# TurboSpin.net
KiCad netlist of a schematic drawn in Altium Designer
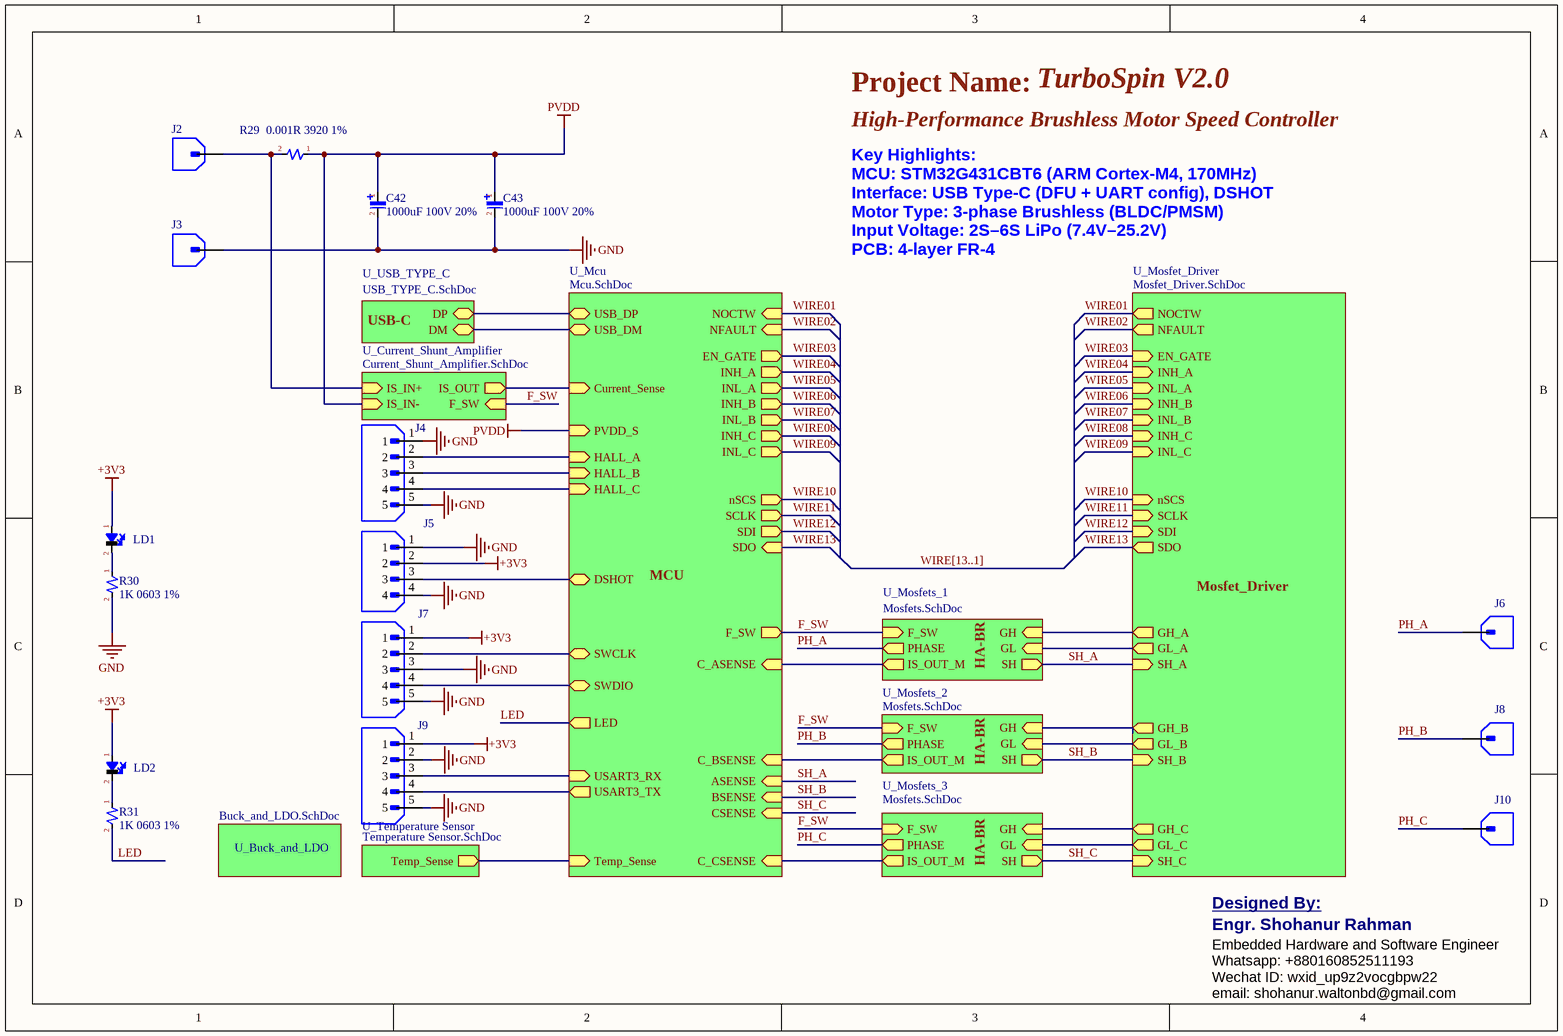
[diagram p0: TurboSpin.SchDoc]

(export (version "E")
  (design (tool "Eeschema 10.0.6"))
  (components
    (comp (ref "C42")
      (value "1000uF 100V 20%")
      (footprint "C_RADIAL")
      (libsource (lib "Walton_EED_13_05_2024") (part "Capacitor{gt}{gt} Polar"))
    )
    (comp (ref "C43")
      (value "1000uF 100V 20%")
      (footprint "C_RADIAL")
      (libsource (lib "Walton_EED_13_05_2024") (part "Capacitor{gt}{gt} Polar"))
    )
    (comp (ref "J2")
      (value "Connector>>B1B")
      (footprint "CN_1P_PAD")
      (description "Connector Header Through Hole 5 position 0.098 (2.50mm)")
      (fields (field (name "MF") "JST Sales") (field (name "MP") "B5B-XH-A"))
      (libsource (lib "Walton_EED_13_05_2024") (part "Connector{gt}{gt}B1B"))
    )
    (comp (ref "J3")
      (value "Connector>>B1B")
      (footprint "CN_1P_PAD")
      (description "Connector Header Through Hole 5 position 0.098 (2.50mm)")
      (fields (field (name "MF") "JST Sales") (field (name "MP") "B5B-XH-A"))
      (libsource (lib "Walton_EED_13_05_2024") (part "Connector{gt}{gt}B1B"))
    )
    (comp (ref "J4")
      (value "Connector>>B5B-XH-A")
      (footprint "CN_HDGC2001WV-S-4")
      (description "Connector Header Through Hole 5 position 0.098 (2.50mm)")
      (fields (field (name "MF") "JST Sales") (field (name "MP") "B5B-XH-A"))
      (libsource (lib "Walton_EED_13_05_2024") (part "Connector{gt}{gt}B5B-XH-A"))
    )
    (comp (ref "J5")
      (value "Connector>>B4B-XH-A")
      (footprint "CN_HDGC2001WV-S-3")
      (description "Connector Header Through Hole 5 position 0.098 (2.50mm)")
      (fields (field (name "MF") "JST Sales") (field (name "MP") "B5B-XH-A"))
      (libsource (lib "Walton_EED_13_05_2024") (part "Connector{gt}{gt}B4B-XH-A"))
    )
    (comp (ref "J6")
      (value "Connector>>B1B")
      (footprint "CN_1P_PAD")
      (description "Connector Header Through Hole 5 position 0.098 (2.50mm)")
      (fields (field (name "MF") "JST Sales") (field (name "MP") "B5B-XH-A"))
      (libsource (lib "") (part "Connector{gt}{gt}B1B_1"))
    )
    (comp (ref "J7")
      (value "Connector>>B5B-XH-A")
      (footprint "CN_HDGC2001WV-S-4")
      (description "Connector Header Through Hole 5 position 0.098 (2.50mm)")
      (fields (field (name "MF") "JST Sales") (field (name "MP") "B5B-XH-A"))
      (libsource (lib "Walton_EED_13_05_2024") (part "Connector{gt}{gt}B5B-XH-A"))
    )
    (comp (ref "J8")
      (value "Connector>>B1B")
      (footprint "CN_1P_PAD")
      (description "Connector Header Through Hole 5 position 0.098 (2.50mm)")
      (fields (field (name "MF") "JST Sales") (field (name "MP") "B5B-XH-A"))
      (libsource (lib "") (part "Connector{gt}{gt}B1B_1"))
    )
    (comp (ref "J9")
      (value "Connector>>B5B-XH-A")
      (footprint "CN_HDGC2001WV-S-4")
      (description "Connector Header Through Hole 5 position 0.098 (2.50mm)")
      (fields (field (name "MF") "JST Sales") (field (name "MP") "B5B-XH-A"))
      (libsource (lib "Walton_EED_13_05_2024") (part "Connector{gt}{gt}B5B-XH-A"))
    )
    (comp (ref "J10")
      (value "Connector>>B1B")
      (footprint "CN_1P_PAD")
      (description "Connector Header Through Hole 5 position 0.098 (2.50mm)")
      (fields (field (name "MF") "JST Sales") (field (name "MP") "B5B-XH-A"))
      (libsource (lib "") (part "Connector{gt}{gt}B1B_1"))
    )
    (comp (ref "LD1")
      (value "1.8Vf  25mA  5mW")
      (footprint "LED_0603_red")
      (libsource (lib "Walton_EED_13_05_2024") (part "LED{gt}{gt} General Purpose"))
    )
    (comp (ref "LD2")
      (value "1.8Vf  25mA  5mW")
      (footprint "LED_0603_red")
      (libsource (lib "Walton_EED_13_05_2024") (part "LED{gt}{gt} General Purpose"))
    )
    (comp (ref "R29")
      (value "0.001R 3920 1%")
      (footprint "R_3920")
      (description "RES 0603 20%")
      (libsource (lib "Walton_EED") (part "Resistor{gt}{gt} General Purpose"))
    )
    (comp (ref "R30")
      (value "1K 0603 1%")
      (footprint "R_0603")
      (description "RES 0603 20%")
      (libsource (lib "Walton_EED") (part "Resistor{gt}{gt} General Purpose"))
    )
    (comp (ref "R31")
      (value "1K 0603 1%")
      (footprint "R_0603")
      (description "RES 0603 20%")
      (libsource (lib "Walton_EED") (part "Resistor{gt}{gt} General Purpose"))
    )
  )
  (nets
    (net (code "10") (name "+3V3") (class "Default")
      (node (ref "J5") (pin "2") (pinfunction "2_2") (pintype "passive"))
      (node (ref "J7") (pin "1") (pinfunction "1_1") (pintype "passive"))
      (node (ref "J9") (pin "1") (pinfunction "1_1") (pintype "passive"))
      (node (ref "LD1") (pin "1") (pinfunction "vdd_1") (pintype "passive"))
      (node (ref "LD2") (pin "1") (pinfunction "vdd_1") (pintype "passive"))
    )
    (net (code "13") (name "/DSHOT") (class "Default")
      (node (ref "J5") (pin "3") (pinfunction "3_3") (pintype "passive"))
    )
    (net (code "21") (name "/HALL_A") (class "Default")
      (node (ref "J4") (pin "2") (pinfunction "2_2") (pintype "passive"))
    )
    (net (code "22") (name "/HALL_B") (class "Default")
      (node (ref "J4") (pin "3") (pinfunction "3_3") (pintype "passive"))
    )
    (net (code "23") (name "/HALL_C") (class "Default")
      (node (ref "J4") (pin "4") (pinfunction "4_4") (pintype "passive"))
    )
    (net (code "24") (name "/IS_IN+") (class "Default")
      (node (ref "J2") (pin "1") (pinfunction "1_1") (pintype "passive"))
      (node (ref "R29") (pin "2") (pinfunction "2_2") (pintype "passive"))
    )
    (net (code "29") (name "/LED") (class "Default")
      (node (ref "R31") (pin "2") (pinfunction "2_2") (pintype "passive"))
    )
    (net (code "30") (name "/PH_A") (class "Default")
      (node (ref "J6") (pin "1") (pinfunction "1_1") (pintype "passive"))
    )
    (net (code "31") (name "/PH_B") (class "Default")
      (node (ref "J8") (pin "1") (pinfunction "1_1") (pintype "passive"))
    )
    (net (code "32") (name "/PH_C") (class "Default")
      (node (ref "J10") (pin "1") (pinfunction "1_1") (pintype "passive"))
    )
    (net (code "37") (name "/SWCLK") (class "Default")
      (node (ref "J7") (pin "2") (pinfunction "2_2") (pintype "passive"))
    )
    (net (code "38") (name "/SWDIO") (class "Default")
      (node (ref "J7") (pin "4") (pinfunction "4_4") (pintype "passive"))
    )
    (net (code "40") (name "/USART3_RX") (class "Default")
      (node (ref "J9") (pin "3") (pinfunction "3_3") (pintype "passive"))
    )
    (net (code "41") (name "/USART3_TX") (class "Default")
      (node (ref "J9") (pin "4") (pinfunction "4_4") (pintype "passive"))
    )
    (net (code "56") (name "GND") (class "Default")
      (node (ref "C42") (pin "2") (pinfunction "2_2") (pintype "passive"))
      (node (ref "C43") (pin "2") (pinfunction "2_2") (pintype "passive"))
      (node (ref "J3") (pin "1") (pinfunction "1_1") (pintype "passive"))
      (node (ref "J4") (pin "1") (pinfunction "1_1") (pintype "passive"))
      (node (ref "J4") (pin "5") (pinfunction "5_5") (pintype "passive"))
      (node (ref "J5") (pin "1") (pinfunction "1_1") (pintype "passive"))
      (node (ref "J5") (pin "4") (pinfunction "4_4") (pintype "passive"))
      (node (ref "J7") (pin "3") (pinfunction "3_3") (pintype "passive"))
      (node (ref "J7") (pin "5") (pinfunction "5_5") (pintype "passive"))
      (node (ref "J9") (pin "2") (pinfunction "2_2") (pintype "passive"))
      (node (ref "J9") (pin "5") (pinfunction "5_5") (pintype "passive"))
      (node (ref "R30") (pin "2") (pinfunction "2_2") (pintype "passive"))
    )
    (net (code "57") (name "Net-(LD1-vss)") (class "Default")
      (node (ref "LD1") (pin "2") (pinfunction "vss_2") (pintype "passive"))
      (node (ref "R30") (pin "1") (pinfunction "1_1") (pintype "passive"))
    )
    (net (code "58") (name "Net-(LD2-vss)") (class "Default")
      (node (ref "LD2") (pin "2") (pinfunction "vss_2") (pintype "passive"))
      (node (ref "R31") (pin "1") (pinfunction "1_1") (pintype "passive"))
    )
    (net (code "59") (name "PVDD") (class "Default")
      (node (ref "C42") (pin "1") (pinfunction "1_1") (pintype "passive"))
      (node (ref "C43") (pin "1") (pinfunction "1_1") (pintype "passive"))
      (node (ref "R29") (pin "1") (pinfunction "1_1") (pintype "passive"))
    )
  )
)
